# InSwitchLEDs.net
KiCad netlist of a schematic drawn in Altium Designer
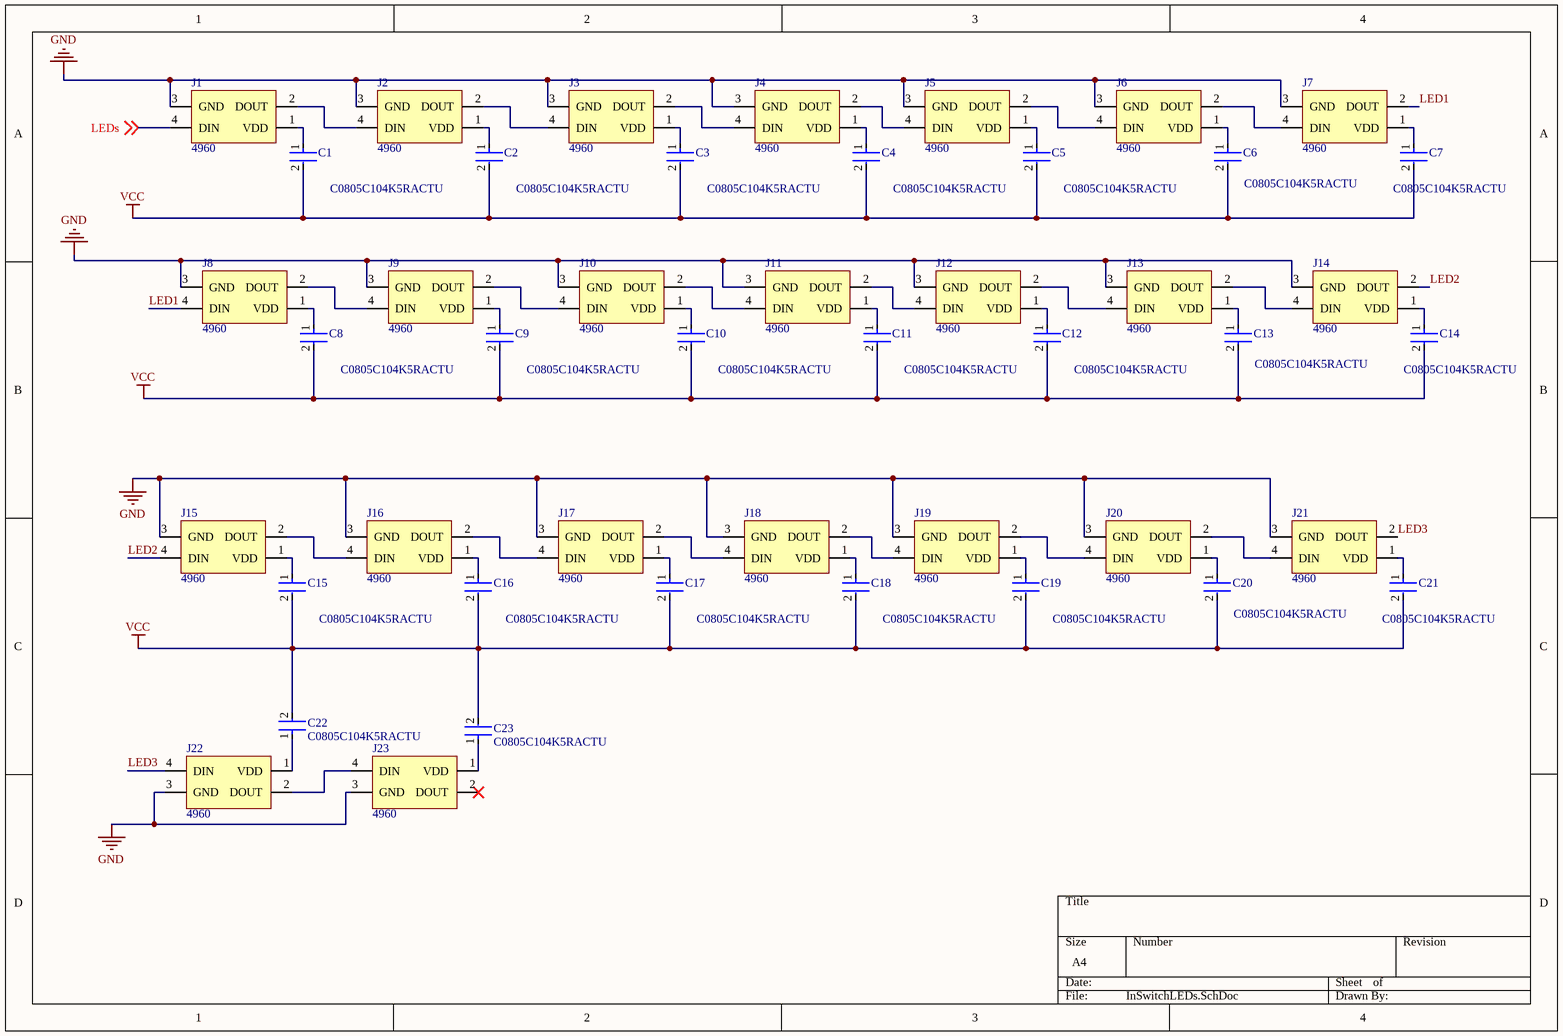
[diagram p0: InSwitchLEDs.SchDoc]

(export (version "E")
  (design (tool "Eeschema 10.0.6"))
  (components
    (comp (ref "C1")
      (value "C0805C104K5RACTU")
      (footprint "FP-C0805C-DN-MFG")
      (description "CAP CER 0.1UF 50V X7R 0805")
      (fields
        (field (name "MANUFACTURER") "KEMET")
        (field (name "OCTOPART") "https://octopart.com/c0805c104k5ractu-kemet-143926")
      )
      (libsource (lib "Altium Content Vault") (part "b4654b650e69147ec39a6b967a45e02"))
    )
    (comp (ref "C2")
      (value "C0805C104K5RACTU")
      (footprint "FP-C0805C-DN-MFG")
      (description "CAP CER 0.1UF 50V X7R 0805")
      (fields
        (field (name "MANUFACTURER") "KEMET")
        (field (name "OCTOPART") "https://octopart.com/c0805c104k5ractu-kemet-143926")
      )
      (libsource (lib "Altium Content Vault") (part "b4654b650e69147ec39a6b967a45e02"))
    )
    (comp (ref "C3")
      (value "C0805C104K5RACTU")
      (footprint "FP-C0805C-DN-MFG")
      (description "CAP CER 0.1UF 50V X7R 0805")
      (fields
        (field (name "MANUFACTURER") "KEMET")
        (field (name "OCTOPART") "https://octopart.com/c0805c104k5ractu-kemet-143926")
      )
      (libsource (lib "Altium Content Vault") (part "b4654b650e69147ec39a6b967a45e02"))
    )
    (comp (ref "C4")
      (value "C0805C104K5RACTU")
      (footprint "FP-C0805C-DN-MFG")
      (description "CAP CER 0.1UF 50V X7R 0805")
      (fields
        (field (name "MANUFACTURER") "KEMET")
        (field (name "OCTOPART") "https://octopart.com/c0805c104k5ractu-kemet-143926")
      )
      (libsource (lib "Altium Content Vault") (part "b4654b650e69147ec39a6b967a45e02"))
    )
    (comp (ref "C5")
      (value "C0805C104K5RACTU")
      (footprint "FP-C0805C-DN-MFG")
      (description "CAP CER 0.1UF 50V X7R 0805")
      (fields
        (field (name "MANUFACTURER") "KEMET")
        (field (name "OCTOPART") "https://octopart.com/c0805c104k5ractu-kemet-143926")
      )
      (libsource (lib "Altium Content Vault") (part "b4654b650e69147ec39a6b967a45e02"))
    )
    (comp (ref "C6")
      (value "C0805C104K5RACTU")
      (footprint "FP-C0805C-DN-MFG")
      (description "CAP CER 0.1UF 50V X7R 0805")
      (fields
        (field (name "MANUFACTURER") "KEMET")
        (field (name "OCTOPART") "https://octopart.com/c0805c104k5ractu-kemet-143926")
      )
      (libsource (lib "Altium Content Vault") (part "b4654b650e69147ec39a6b967a45e02"))
    )
    (comp (ref "C7")
      (value "C0805C104K5RACTU")
      (footprint "FP-C0805C-DN-MFG")
      (description "CAP CER 0.1UF 50V X7R 0805")
      (fields
        (field (name "MANUFACTURER") "KEMET")
        (field (name "OCTOPART") "https://octopart.com/c0805c104k5ractu-kemet-143926")
      )
      (libsource (lib "Altium Content Vault") (part "b4654b650e69147ec39a6b967a45e02"))
    )
    (comp (ref "C8")
      (value "C0805C104K5RACTU")
      (footprint "FP-C0805C-DN-MFG")
      (description "CAP CER 0.1UF 50V X7R 0805")
      (fields
        (field (name "MANUFACTURER") "KEMET")
        (field (name "OCTOPART") "https://octopart.com/c0805c104k5ractu-kemet-143926")
      )
      (libsource (lib "Altium Content Vault") (part "b4654b650e69147ec39a6b967a45e02"))
    )
    (comp (ref "C9")
      (value "C0805C104K5RACTU")
      (footprint "FP-C0805C-DN-MFG")
      (description "CAP CER 0.1UF 50V X7R 0805")
      (fields
        (field (name "MANUFACTURER") "KEMET")
        (field (name "OCTOPART") "https://octopart.com/c0805c104k5ractu-kemet-143926")
      )
      (libsource (lib "Altium Content Vault") (part "b4654b650e69147ec39a6b967a45e02"))
    )
    (comp (ref "C10")
      (value "C0805C104K5RACTU")
      (footprint "FP-C0805C-DN-MFG")
      (description "CAP CER 0.1UF 50V X7R 0805")
      (fields
        (field (name "MANUFACTURER") "KEMET")
        (field (name "OCTOPART") "https://octopart.com/c0805c104k5ractu-kemet-143926")
      )
      (libsource (lib "Altium Content Vault") (part "b4654b650e69147ec39a6b967a45e02"))
    )
    (comp (ref "C11")
      (value "C0805C104K5RACTU")
      (footprint "FP-C0805C-DN-MFG")
      (description "CAP CER 0.1UF 50V X7R 0805")
      (fields
        (field (name "MANUFACTURER") "KEMET")
        (field (name "OCTOPART") "https://octopart.com/c0805c104k5ractu-kemet-143926")
      )
      (libsource (lib "Altium Content Vault") (part "b4654b650e69147ec39a6b967a45e02"))
    )
    (comp (ref "C12")
      (value "C0805C104K5RACTU")
      (footprint "FP-C0805C-DN-MFG")
      (description "CAP CER 0.1UF 50V X7R 0805")
      (fields
        (field (name "MANUFACTURER") "KEMET")
        (field (name "OCTOPART") "https://octopart.com/c0805c104k5ractu-kemet-143926")
      )
      (libsource (lib "Altium Content Vault") (part "b4654b650e69147ec39a6b967a45e02"))
    )
    (comp (ref "C13")
      (value "C0805C104K5RACTU")
      (footprint "FP-C0805C-DN-MFG")
      (description "CAP CER 0.1UF 50V X7R 0805")
      (fields
        (field (name "MANUFACTURER") "KEMET")
        (field (name "OCTOPART") "https://octopart.com/c0805c104k5ractu-kemet-143926")
      )
      (libsource (lib "Altium Content Vault") (part "b4654b650e69147ec39a6b967a45e02"))
    )
    (comp (ref "C14")
      (value "C0805C104K5RACTU")
      (footprint "FP-C0805C-DN-MFG")
      (description "CAP CER 0.1UF 50V X7R 0805")
      (fields
        (field (name "MANUFACTURER") "KEMET")
        (field (name "OCTOPART") "https://octopart.com/c0805c104k5ractu-kemet-143926")
      )
      (libsource (lib "Altium Content Vault") (part "b4654b650e69147ec39a6b967a45e02"))
    )
    (comp (ref "C15")
      (value "C0805C104K5RACTU")
      (footprint "FP-C0805C-DN-MFG")
      (description "CAP CER 0.1UF 50V X7R 0805")
      (fields
        (field (name "MANUFACTURER") "KEMET")
        (field (name "OCTOPART") "https://octopart.com/c0805c104k5ractu-kemet-143926")
      )
      (libsource (lib "Altium Content Vault") (part "b4654b650e69147ec39a6b967a45e02"))
    )
    (comp (ref "C16")
      (value "C0805C104K5RACTU")
      (footprint "FP-C0805C-DN-MFG")
      (description "CAP CER 0.1UF 50V X7R 0805")
      (fields
        (field (name "MANUFACTURER") "KEMET")
        (field (name "OCTOPART") "https://octopart.com/c0805c104k5ractu-kemet-143926")
      )
      (libsource (lib "Altium Content Vault") (part "b4654b650e69147ec39a6b967a45e02"))
    )
    (comp (ref "C17")
      (value "C0805C104K5RACTU")
      (footprint "FP-C0805C-DN-MFG")
      (description "CAP CER 0.1UF 50V X7R 0805")
      (fields
        (field (name "MANUFACTURER") "KEMET")
        (field (name "OCTOPART") "https://octopart.com/c0805c104k5ractu-kemet-143926")
      )
      (libsource (lib "Altium Content Vault") (part "b4654b650e69147ec39a6b967a45e02"))
    )
    (comp (ref "C18")
      (value "C0805C104K5RACTU")
      (footprint "FP-C0805C-DN-MFG")
      (description "CAP CER 0.1UF 50V X7R 0805")
      (fields
        (field (name "MANUFACTURER") "KEMET")
        (field (name "OCTOPART") "https://octopart.com/c0805c104k5ractu-kemet-143926")
      )
      (libsource (lib "Altium Content Vault") (part "b4654b650e69147ec39a6b967a45e02"))
    )
    (comp (ref "C19")
      (value "C0805C104K5RACTU")
      (footprint "FP-C0805C-DN-MFG")
      (description "CAP CER 0.1UF 50V X7R 0805")
      (fields
        (field (name "MANUFACTURER") "KEMET")
        (field (name "OCTOPART") "https://octopart.com/c0805c104k5ractu-kemet-143926")
      )
      (libsource (lib "Altium Content Vault") (part "b4654b650e69147ec39a6b967a45e02"))
    )
    (comp (ref "C20")
      (value "C0805C104K5RACTU")
      (footprint "FP-C0805C-DN-MFG")
      (description "CAP CER 0.1UF 50V X7R 0805")
      (fields
        (field (name "MANUFACTURER") "KEMET")
        (field (name "OCTOPART") "https://octopart.com/c0805c104k5ractu-kemet-143926")
      )
      (libsource (lib "Altium Content Vault") (part "b4654b650e69147ec39a6b967a45e02"))
    )
    (comp (ref "C21")
      (value "C0805C104K5RACTU")
      (footprint "FP-C0805C-DN-MFG")
      (description "CAP CER 0.1UF 50V X7R 0805")
      (fields
        (field (name "MANUFACTURER") "KEMET")
        (field (name "OCTOPART") "https://octopart.com/c0805c104k5ractu-kemet-143926")
      )
      (libsource (lib "Altium Content Vault") (part "b4654b650e69147ec39a6b967a45e02"))
    )
    (comp (ref "C22")
      (value "C0805C104K5RACTU")
      (footprint "FP-C0805C-DN-MFG")
      (description "CAP CER 0.1UF 50V X7R 0805")
      (fields
        (field (name "MANUFACTURER") "KEMET")
        (field (name "OCTOPART") "https://octopart.com/c0805c104k5ractu-kemet-143926")
      )
      (libsource (lib "Altium Content Vault") (part "b4654b650e69147ec39a6b967a45e02"))
    )
    (comp (ref "C23")
      (value "C0805C104K5RACTU")
      (footprint "FP-C0805C-DN-MFG")
      (description "CAP CER 0.1UF 50V X7R 0805")
      (fields
        (field (name "MANUFACTURER") "KEMET")
        (field (name "OCTOPART") "https://octopart.com/c0805c104k5ractu-kemet-143926")
      )
      (libsource (lib "Altium Content Vault") (part "b4654b650e69147ec39a6b967a45e02"))
    )
    (comp (ref "J1")
      (value "4960")
      (footprint "4960_Adafruit")
      (libsource (lib "4960 LED") (part "Component_1"))
    )
    (comp (ref "J2")
      (value "4960")
      (footprint "4960_Adafruit")
      (libsource (lib "4960 LED") (part "Component_1"))
    )
    (comp (ref "J3")
      (value "4960")
      (footprint "4960_Adafruit")
      (libsource (lib "4960 LED") (part "Component_1"))
    )
    (comp (ref "J4")
      (value "4960")
      (footprint "4960_Adafruit")
      (libsource (lib "4960 LED") (part "Component_1"))
    )
    (comp (ref "J5")
      (value "4960")
      (footprint "4960_Adafruit")
      (libsource (lib "4960 LED") (part "Component_1"))
    )
    (comp (ref "J6")
      (value "4960")
      (footprint "4960_Adafruit")
      (libsource (lib "4960 LED") (part "Component_1"))
    )
    (comp (ref "J7")
      (value "4960")
      (footprint "4960_Adafruit")
      (libsource (lib "4960 LED") (part "Component_1"))
    )
    (comp (ref "J8")
      (value "4960")
      (footprint "4960_Adafruit")
      (libsource (lib "4960 LED") (part "Component_1"))
    )
    (comp (ref "J9")
      (value "4960")
      (footprint "4960_Adafruit")
      (libsource (lib "4960 LED") (part "Component_1"))
    )
    (comp (ref "J10")
      (value "4960")
      (footprint "4960_Adafruit")
      (libsource (lib "4960 LED") (part "Component_1"))
    )
    (comp (ref "J11")
      (value "4960")
      (footprint "4960_Adafruit")
      (libsource (lib "4960 LED") (part "Component_1"))
    )
    (comp (ref "J12")
      (value "4960")
      (footprint "4960_Adafruit")
      (libsource (lib "4960 LED") (part "Component_1"))
    )
    (comp (ref "J13")
      (value "4960")
      (footprint "4960_Adafruit")
      (libsource (lib "4960 LED") (part "Component_1"))
    )
    (comp (ref "J14")
      (value "4960")
      (footprint "4960_Adafruit")
      (libsource (lib "4960 LED") (part "Component_1"))
    )
    (comp (ref "J15")
      (value "4960")
      (footprint "4960_Adafruit")
      (libsource (lib "4960 LED") (part "Component_1"))
    )
    (comp (ref "J16")
      (value "4960")
      (footprint "4960_Adafruit")
      (libsource (lib "4960 LED") (part "Component_1"))
    )
    (comp (ref "J17")
      (value "4960")
      (footprint "4960_Adafruit")
      (libsource (lib "4960 LED") (part "Component_1"))
    )
    (comp (ref "J18")
      (value "4960")
      (footprint "4960_Adafruit")
      (libsource (lib "4960 LED") (part "Component_1"))
    )
    (comp (ref "J19")
      (value "4960")
      (footprint "4960_Adafruit")
      (libsource (lib "4960 LED") (part "Component_1"))
    )
    (comp (ref "J20")
      (value "4960")
      (footprint "4960_Adafruit")
      (libsource (lib "4960 LED") (part "Component_1"))
    )
    (comp (ref "J21")
      (value "4960")
      (footprint "4960_Adafruit")
      (libsource (lib "4960 LED") (part "Component_1"))
    )
    (comp (ref "J22") (value "4960") (footprint "4960_Adafruit") (libsource (lib "") (part "Component_1_1")))
    (comp (ref "J23") (value "4960") (footprint "4960_Adafruit") (libsource (lib "") (part "Component_1_1")))
  )
  (nets
    (net (code "1") (name "/LED1") (class "Default")
      (node (ref "J7") (pin "2") (pinfunction "DOUT_2") (pintype "passive"))
      (node (ref "J8") (pin "4") (pinfunction "DIN_4") (pintype "passive"))
    )
    (net (code "2") (name "/LED2") (class "Default")
      (node (ref "J14") (pin "2") (pinfunction "DOUT_2") (pintype "passive"))
      (node (ref "J15") (pin "4") (pinfunction "DIN_4") (pintype "passive"))
    )
    (net (code "3") (name "/LED3") (class "Default")
      (node (ref "J21") (pin "2") (pinfunction "DOUT_2") (pintype "passive"))
      (node (ref "J22") (pin "4") (pinfunction "DIN_4") (pintype "passive"))
    )
    (net (code "4") (name "GND") (class "Default")
      (node (ref "J1") (pin "3") (pinfunction "GND_3") (pintype "passive"))
      (node (ref "J10") (pin "3") (pinfunction "GND_3") (pintype "passive"))
      (node (ref "J11") (pin "3") (pinfunction "GND_3") (pintype "passive"))
      (node (ref "J12") (pin "3") (pinfunction "GND_3") (pintype "passive"))
      (node (ref "J13") (pin "3") (pinfunction "GND_3") (pintype "passive"))
      (node (ref "J14") (pin "3") (pinfunction "GND_3") (pintype "passive"))
      (node (ref "J15") (pin "3") (pinfunction "GND_3") (pintype "passive"))
      (node (ref "J16") (pin "3") (pinfunction "GND_3") (pintype "passive"))
      (node (ref "J17") (pin "3") (pinfunction "GND_3") (pintype "passive"))
      (node (ref "J18") (pin "3") (pinfunction "GND_3") (pintype "passive"))
      (node (ref "J19") (pin "3") (pinfunction "GND_3") (pintype "passive"))
      (node (ref "J2") (pin "3") (pinfunction "GND_3") (pintype "passive"))
      (node (ref "J20") (pin "3") (pinfunction "GND_3") (pintype "passive"))
      (node (ref "J21") (pin "3") (pinfunction "GND_3") (pintype "passive"))
      (node (ref "J22") (pin "3") (pinfunction "GND_3") (pintype "passive"))
      (node (ref "J23") (pin "3") (pinfunction "GND_3") (pintype "passive"))
      (node (ref "J3") (pin "3") (pinfunction "GND_3") (pintype "passive"))
      (node (ref "J4") (pin "3") (pinfunction "GND_3") (pintype "passive"))
      (node (ref "J5") (pin "3") (pinfunction "GND_3") (pintype "passive"))
      (node (ref "J6") (pin "3") (pinfunction "GND_3") (pintype "passive"))
      (node (ref "J7") (pin "3") (pinfunction "GND_3") (pintype "passive"))
      (node (ref "J8") (pin "3") (pinfunction "GND_3") (pintype "passive"))
      (node (ref "J9") (pin "3") (pinfunction "GND_3") (pintype "passive"))
    )
    (net (code "5") (name "LEDs") (class "Default")
      (node (ref "J1") (pin "4") (pinfunction "DIN_4") (pintype "passive"))
    )
    (net (code "6") (name "Net-(J1-DOUT)") (class "Default")
      (node (ref "J1") (pin "2") (pinfunction "DOUT_2") (pintype "passive"))
      (node (ref "J2") (pin "4") (pinfunction "DIN_4") (pintype "passive"))
    )
    (net (code "7") (name "Net-(J1-VDD)") (class "Default")
      (node (ref "C1") (pin "1") (pinfunction "1_1") (pintype "passive"))
      (node (ref "J1") (pin "1") (pinfunction "VDD_1") (pintype "passive"))
    )
    (net (code "8") (name "Net-(J2-DOUT)") (class "Default")
      (node (ref "J2") (pin "2") (pinfunction "DOUT_2") (pintype "passive"))
      (node (ref "J3") (pin "4") (pinfunction "DIN_4") (pintype "passive"))
    )
    (net (code "9") (name "Net-(J2-VDD)") (class "Default")
      (node (ref "C2") (pin "1") (pinfunction "1_1") (pintype "passive"))
      (node (ref "J2") (pin "1") (pinfunction "VDD_1") (pintype "passive"))
    )
    (net (code "10") (name "Net-(J3-DOUT)") (class "Default")
      (node (ref "J3") (pin "2") (pinfunction "DOUT_2") (pintype "passive"))
      (node (ref "J4") (pin "4") (pinfunction "DIN_4") (pintype "passive"))
    )
    (net (code "11") (name "Net-(J3-VDD)") (class "Default")
      (node (ref "C3") (pin "1") (pinfunction "1_1") (pintype "passive"))
      (node (ref "J3") (pin "1") (pinfunction "VDD_1") (pintype "passive"))
    )
    (net (code "12") (name "Net-(J4-DOUT)") (class "Default")
      (node (ref "J4") (pin "2") (pinfunction "DOUT_2") (pintype "passive"))
      (node (ref "J5") (pin "4") (pinfunction "DIN_4") (pintype "passive"))
    )
    (net (code "13") (name "Net-(J4-VDD)") (class "Default")
      (node (ref "C4") (pin "1") (pinfunction "1_1") (pintype "passive"))
      (node (ref "J4") (pin "1") (pinfunction "VDD_1") (pintype "passive"))
    )
    (net (code "14") (name "Net-(J5-DOUT)") (class "Default")
      (node (ref "J5") (pin "2") (pinfunction "DOUT_2") (pintype "passive"))
      (node (ref "J6") (pin "4") (pinfunction "DIN_4") (pintype "passive"))
    )
    (net (code "15") (name "Net-(J5-VDD)") (class "Default")
      (node (ref "C5") (pin "1") (pinfunction "1_1") (pintype "passive"))
      (node (ref "J5") (pin "1") (pinfunction "VDD_1") (pintype "passive"))
    )
    (net (code "16") (name "Net-(J6-DOUT)") (class "Default")
      (node (ref "J6") (pin "2") (pinfunction "DOUT_2") (pintype "passive"))
      (node (ref "J7") (pin "4") (pinfunction "DIN_4") (pintype "passive"))
    )
    (net (code "17") (name "Net-(J6-VDD)") (class "Default")
      (node (ref "C6") (pin "1") (pinfunction "1_1") (pintype "passive"))
      (node (ref "J6") (pin "1") (pinfunction "VDD_1") (pintype "passive"))
    )
    (net (code "18") (name "Net-(J7-VDD)") (class "Default")
      (node (ref "C7") (pin "1") (pinfunction "1_1") (pintype "passive"))
      (node (ref "J7") (pin "1") (pinfunction "VDD_1") (pintype "passive"))
    )
    (net (code "19") (name "Net-(J8-DOUT)") (class "Default")
      (node (ref "J8") (pin "2") (pinfunction "DOUT_2") (pintype "passive"))
      (node (ref "J9") (pin "4") (pinfunction "DIN_4") (pintype "passive"))
    )
    (net (code "20") (name "Net-(J8-VDD)") (class "Default")
      (node (ref "C8") (pin "1") (pinfunction "1_1") (pintype "passive"))
      (node (ref "J8") (pin "1") (pinfunction "VDD_1") (pintype "passive"))
    )
    (net (code "21") (name "Net-(J9-VDD)") (class "Default")
      (node (ref "C9") (pin "1") (pinfunction "1_1") (pintype "passive"))
      (node (ref "J9") (pin "1") (pinfunction "VDD_1") (pintype "passive"))
    )
    (net (code "22") (name "Net-(J10-DIN)") (class "Default")
      (node (ref "J10") (pin "4") (pinfunction "DIN_4") (pintype "passive"))
      (node (ref "J9") (pin "2") (pinfunction "DOUT_2") (pintype "passive"))
    )
    (net (code "23") (name "Net-(J10-DOUT)") (class "Default")
      (node (ref "J10") (pin "2") (pinfunction "DOUT_2") (pintype "passive"))
      (node (ref "J11") (pin "4") (pinfunction "DIN_4") (pintype "passive"))
    )
    (net (code "24") (name "Net-(J10-VDD)") (class "Default")
      (node (ref "C10") (pin "1") (pinfunction "1_1") (pintype "passive"))
      (node (ref "J10") (pin "1") (pinfunction "VDD_1") (pintype "passive"))
    )
    (net (code "25") (name "Net-(J11-DOUT)") (class "Default")
      (node (ref "J11") (pin "2") (pinfunction "DOUT_2") (pintype "passive"))
      (node (ref "J12") (pin "4") (pinfunction "DIN_4") (pintype "passive"))
    )
    (net (code "26") (name "Net-(J11-VDD)") (class "Default")
      (node (ref "C11") (pin "1") (pinfunction "1_1") (pintype "passive"))
      (node (ref "J11") (pin "1") (pinfunction "VDD_1") (pintype "passive"))
    )
    (net (code "27") (name "Net-(J12-DOUT)") (class "Default")
      (node (ref "J12") (pin "2") (pinfunction "DOUT_2") (pintype "passive"))
      (node (ref "J13") (pin "4") (pinfunction "DIN_4") (pintype "passive"))
    )
    (net (code "28") (name "Net-(J12-VDD)") (class "Default")
      (node (ref "C12") (pin "1") (pinfunction "1_1") (pintype "passive"))
      (node (ref "J12") (pin "1") (pinfunction "VDD_1") (pintype "passive"))
    )
    (net (code "29") (name "Net-(J13-DOUT)") (class "Default")
      (node (ref "J13") (pin "2") (pinfunction "DOUT_2") (pintype "passive"))
      (node (ref "J14") (pin "4") (pinfunction "DIN_4") (pintype "passive"))
    )
    (net (code "30") (name "Net-(J13-VDD)") (class "Default")
      (node (ref "C13") (pin "1") (pinfunction "1_1") (pintype "passive"))
      (node (ref "J13") (pin "1") (pinfunction "VDD_1") (pintype "passive"))
    )
    (net (code "31") (name "Net-(J14-VDD)") (class "Default")
      (node (ref "C14") (pin "1") (pinfunction "1_1") (pintype "passive"))
      (node (ref "J14") (pin "1") (pinfunction "VDD_1") (pintype "passive"))
    )
    (net (code "32") (name "Net-(J15-DOUT)") (class "Default")
      (node (ref "J15") (pin "2") (pinfunction "DOUT_2") (pintype "passive"))
      (node (ref "J16") (pin "4") (pinfunction "DIN_4") (pintype "passive"))
    )
    (net (code "33") (name "Net-(J15-VDD)") (class "Default")
      (node (ref "C15") (pin "1") (pinfunction "1_1") (pintype "passive"))
      (node (ref "J15") (pin "1") (pinfunction "VDD_1") (pintype "passive"))
    )
    (net (code "34") (name "Net-(J16-DOUT)") (class "Default")
      (node (ref "J16") (pin "2") (pinfunction "DOUT_2") (pintype "passive"))
      (node (ref "J17") (pin "4") (pinfunction "DIN_4") (pintype "passive"))
    )
    (net (code "35") (name "Net-(J16-VDD)") (class "Default")
      (node (ref "C16") (pin "1") (pinfunction "1_1") (pintype "passive"))
      (node (ref "J16") (pin "1") (pinfunction "VDD_1") (pintype "passive"))
    )
    (net (code "36") (name "Net-(J17-DOUT)") (class "Default")
      (node (ref "J17") (pin "2") (pinfunction "DOUT_2") (pintype "passive"))
      (node (ref "J18") (pin "4") (pinfunction "DIN_4") (pintype "passive"))
    )
    (net (code "37") (name "Net-(J17-VDD)") (class "Default")
      (node (ref "C17") (pin "1") (pinfunction "1_1") (pintype "passive"))
      (node (ref "J17") (pin "1") (pinfunction "VDD_1") (pintype "passive"))
    )
    (net (code "38") (name "Net-(J18-DOUT)") (class "Default")
      (node (ref "J18") (pin "2") (pinfunction "DOUT_2") (pintype "passive"))
      (node (ref "J19") (pin "4") (pinfunction "DIN_4") (pintype "passive"))
    )
    (net (code "39") (name "Net-(J18-VDD)") (class "Default")
      (node (ref "C18") (pin "1") (pinfunction "1_1") (pintype "passive"))
      (node (ref "J18") (pin "1") (pinfunction "VDD_1") (pintype "passive"))
    )
    (net (code "40") (name "Net-(J19-DOUT)") (class "Default")
      (node (ref "J19") (pin "2") (pinfunction "DOUT_2") (pintype "passive"))
      (node (ref "J20") (pin "4") (pinfunction "DIN_4") (pintype "passive"))
    )
    (net (code "41") (name "Net-(J19-VDD)") (class "Default")
      (node (ref "C19") (pin "1") (pinfunction "1_1") (pintype "passive"))
      (node (ref "J19") (pin "1") (pinfunction "VDD_1") (pintype "passive"))
    )
    (net (code "42") (name "Net-(J20-DOUT)") (class "Default")
      (node (ref "J20") (pin "2") (pinfunction "DOUT_2") (pintype "passive"))
      (node (ref "J21") (pin "4") (pinfunction "DIN_4") (pintype "passive"))
    )
    (net (code "43") (name "Net-(J20-VDD)") (class "Default")
      (node (ref "C20") (pin "1") (pinfunction "1_1") (pintype "passive"))
      (node (ref "J20") (pin "1") (pinfunction "VDD_1") (pintype "passive"))
    )
    (net (code "44") (name "Net-(J21-VDD)") (class "Default")
      (node (ref "C21") (pin "1") (pinfunction "1_1") (pintype "passive"))
      (node (ref "J21") (pin "1") (pinfunction "VDD_1") (pintype "passive"))
    )
    (net (code "45") (name "Net-(J22-DOUT)") (class "Default")
      (node (ref "J22") (pin "2") (pinfunction "DOUT_2") (pintype "passive"))
      (node (ref "J23") (pin "4") (pinfunction "DIN_4") (pintype "passive"))
    )
    (net (code "46") (name "Net-(J22-VDD)") (class "Default")
      (node (ref "C22") (pin "1") (pinfunction "1_1") (pintype "passive"))
      (node (ref "J22") (pin "1") (pinfunction "VDD_1") (pintype "passive"))
    )
    (net (code "47") (name "Net-(J23-VDD)") (class "Default")
      (node (ref "C23") (pin "1") (pinfunction "1_1") (pintype "passive"))
      (node (ref "J23") (pin "1") (pinfunction "VDD_1") (pintype "passive"))
    )
    (net (code "48") (name "VCC") (class "Default")
      (node (ref "C1") (pin "2") (pinfunction "2_2") (pintype "passive"))
      (node (ref "C10") (pin "2") (pinfunction "2_2") (pintype "passive"))
      (node (ref "C11") (pin "2") (pinfunction "2_2") (pintype "passive"))
      (node (ref "C12") (pin "2") (pinfunction "2_2") (pintype "passive"))
      (node (ref "C13") (pin "2") (pinfunction "2_2") (pintype "passive"))
      (node (ref "C14") (pin "2") (pinfunction "2_2") (pintype "passive"))
      (node (ref "C15") (pin "2") (pinfunction "2_2") (pintype "passive"))
      (node (ref "C16") (pin "2") (pinfunction "2_2") (pintype "passive"))
      (node (ref "C17") (pin "2") (pinfunction "2_2") (pintype "passive"))
      (node (ref "C18") (pin "2") (pinfunction "2_2") (pintype "passive"))
      (node (ref "C19") (pin "2") (pinfunction "2_2") (pintype "passive"))
      (node (ref "C2") (pin "2") (pinfunction "2_2") (pintype "passive"))
      (node (ref "C20") (pin "2") (pinfunction "2_2") (pintype "passive"))
      (node (ref "C21") (pin "2") (pinfunction "2_2") (pintype "passive"))
      (node (ref "C22") (pin "2") (pinfunction "2_2") (pintype "passive"))
      (node (ref "C23") (pin "2") (pinfunction "2_2") (pintype "passive"))
      (node (ref "C3") (pin "2") (pinfunction "2_2") (pintype "passive"))
      (node (ref "C4") (pin "2") (pinfunction "2_2") (pintype "passive"))
      (node (ref "C5") (pin "2") (pinfunction "2_2") (pintype "passive"))
      (node (ref "C6") (pin "2") (pinfunction "2_2") (pintype "passive"))
      (node (ref "C7") (pin "2") (pinfunction "2_2") (pintype "passive"))
      (node (ref "C8") (pin "2") (pinfunction "2_2") (pintype "passive"))
      (node (ref "C9") (pin "2") (pinfunction "2_2") (pintype "passive"))
    )
    (net (code "49") (name "unconnected-(J23-DOUT-Pad2)") (class "Default")
      (node (ref "J23") (pin "2") (pinfunction "DOUT_2") (pintype "passive+no_connect"))
    )
  )
)
